# Battery-Voltage-Measure.net
KiCad netlist of a schematic drawn in EAGLE
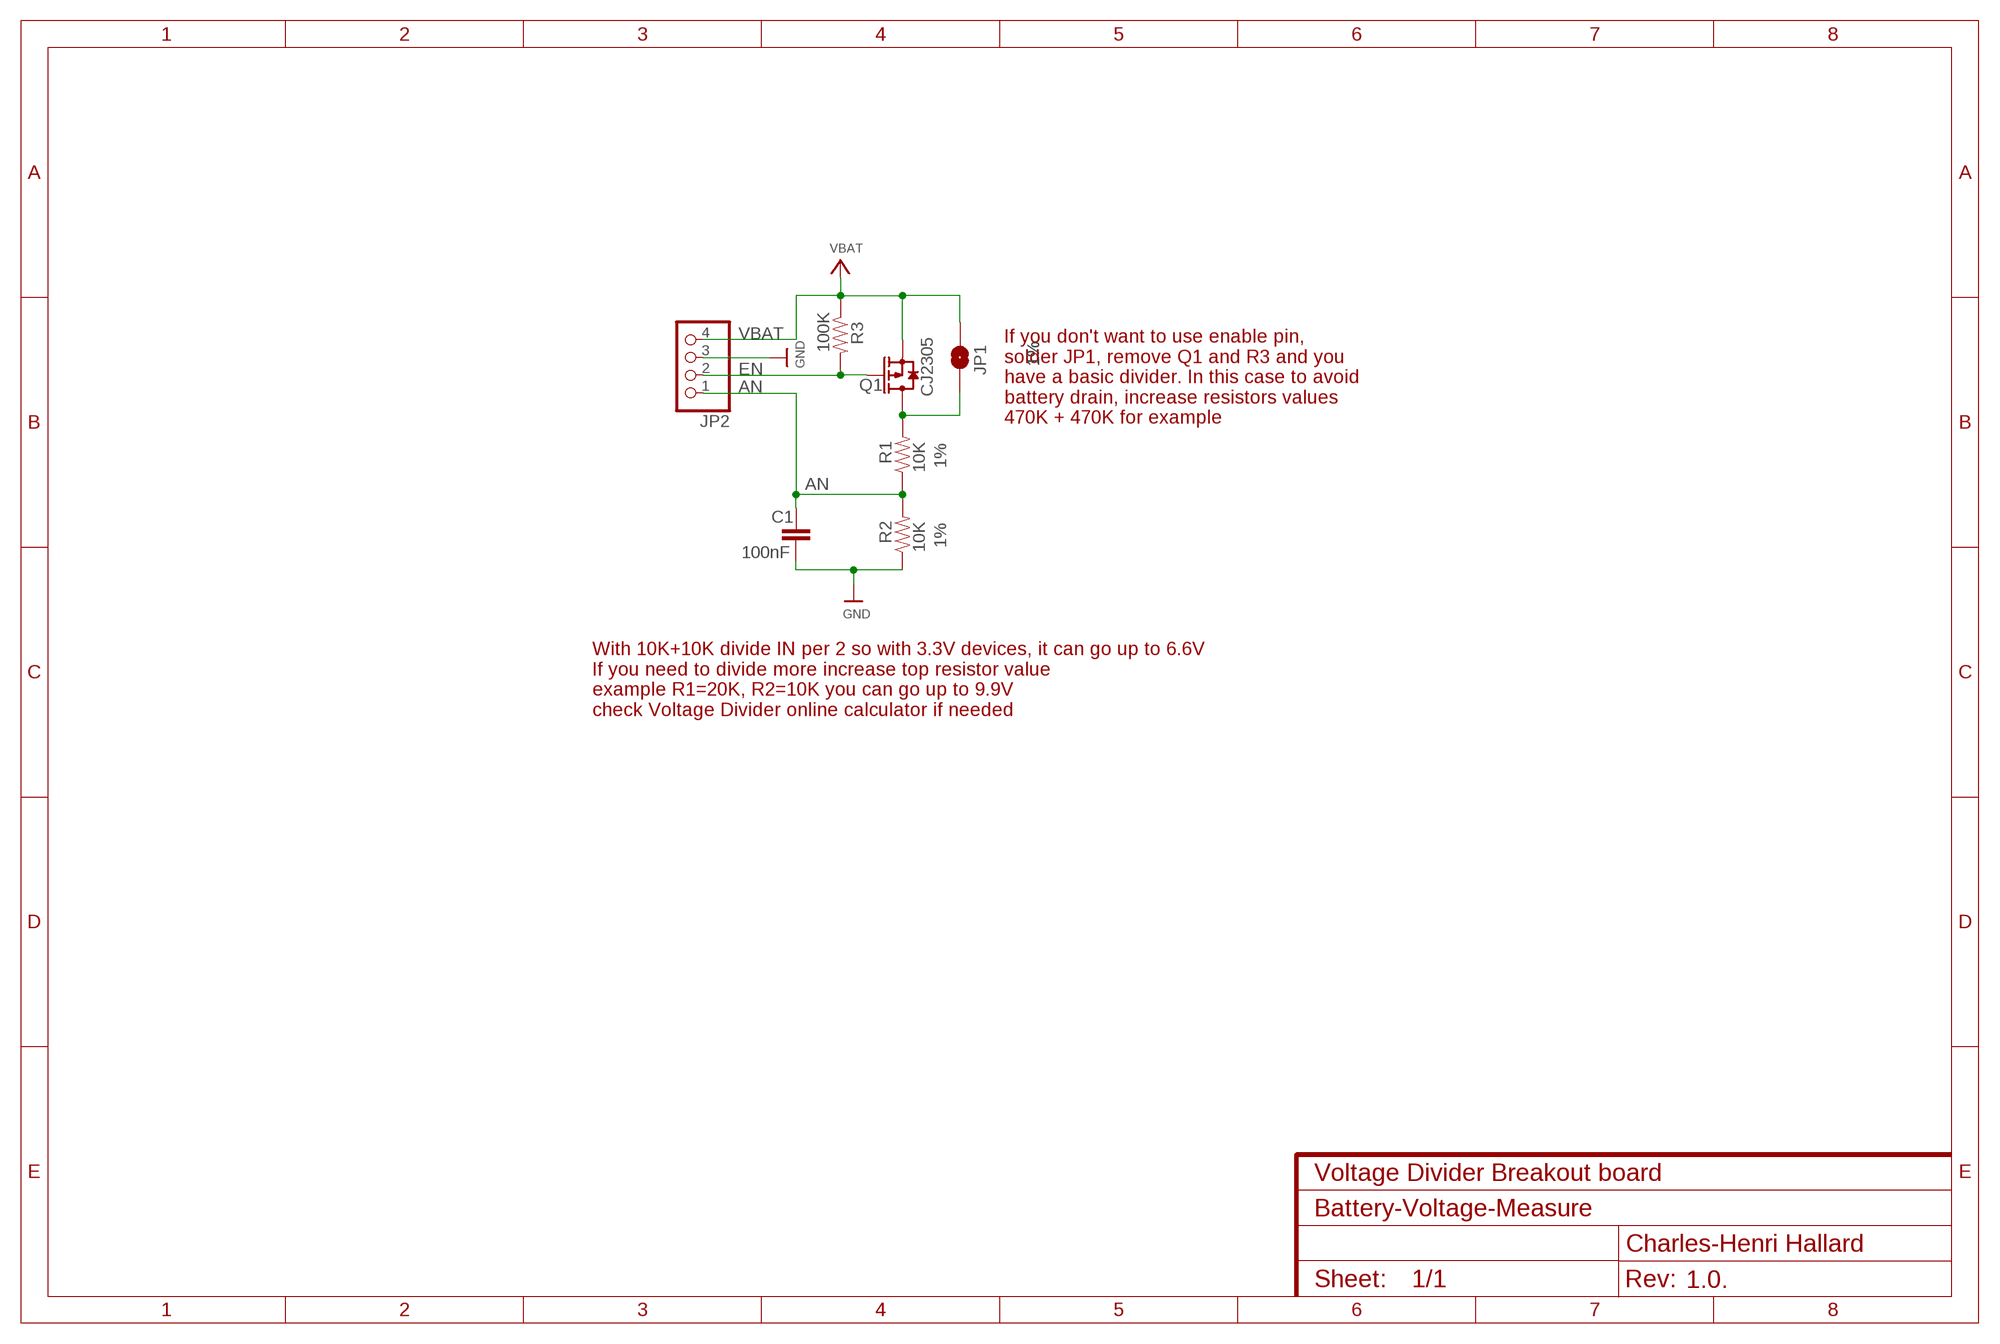
[diagram p0: schematic, sheet 1]

(export (version "E")
  (design (tool "Eeschema 10.0.6"))
  (components
    (comp (ref "C1")
      (value "100nF")
      (footprint "eagle-import:0805-CAP")
      (libsource (lib "eagle-import") (part "CAP0805-CAP"))
    )
    (comp (ref "JP1")
      (value "JUMPER-SMT_2_NO_SILK")
      (footprint "eagle-import:SMT-JUMPER_2_NO_SILK")
      (libsource (lib "eagle-import") (part "JUMPER-SMT_2_NO_SILK"))
    )
    (comp (ref "JP2")
      (value "HEADER-1X476MIL")
      (footprint "eagle-import:1X04_ROUND_76")
      (libsource (lib "eagle-import") (part "HEADER-1X476MIL"))
    )
    (comp (ref "Q1")
      (value "CJ2305")
      (footprint "eagle-import:SOT23")
      (libsource (lib "eagle-import") (part "MOSFET-P-044021001"))
    )
    (comp (ref "R1")
      (value "10K")
      (footprint "eagle-import:0805-RES")
      (libsource (lib "eagle-import") (part "_c2h_RESISTOR0805-RES"))
    )
    (comp (ref "R2")
      (value "10K")
      (footprint "eagle-import:0805-RES")
      (libsource (lib "eagle-import") (part "_c2h_RESISTOR0805-RES"))
    )
    (comp (ref "R3")
      (value "100K")
      (footprint "eagle-import:0805-RES")
      (libsource (lib "eagle-import") (part "RESISTOR0805-RES"))
    )
  )
  (nets
    (net (code "1") (name "/AN") (class "Default")
      (node (ref "C1") (pin "1") (pinfunction "1_1") (pintype "passive"))
      (node (ref "JP2") (pin "1") (pinfunction "1_1") (pintype "passive"))
      (node (ref "R1") (pin "1") (pinfunction "1_1") (pintype "passive"))
      (node (ref "R2") (pin "2") (pinfunction "2_2") (pintype "passive"))
    )
    (net (code "2") (name "/EN") (class "Default")
      (node (ref "JP2") (pin "2") (pinfunction "2_2") (pintype "passive"))
      (node (ref "Q1") (pin "1") (pinfunction "G_1") (pintype "passive"))
      (node (ref "R3") (pin "2") (pinfunction "2_2") (pintype "passive"))
    )
    (net (code "3") (name "GND") (class "Default")
      (node (ref "C1") (pin "2") (pinfunction "2_2") (pintype "passive"))
      (node (ref "JP2") (pin "3") (pinfunction "3_3") (pintype "passive"))
      (node (ref "R2") (pin "1") (pinfunction "1_1") (pintype "passive"))
    )
    (net (code "4") (name "Net-(Q1-D)") (class "Default")
      (node (ref "JP1") (pin "1") (pinfunction "1_1") (pintype "passive"))
      (node (ref "Q1") (pin "3") (pinfunction "D_3") (pintype "passive"))
      (node (ref "R1") (pin "2") (pinfunction "2_2") (pintype "passive"))
    )
    (net (code "5") (name "VBAT") (class "Default")
      (node (ref "JP1") (pin "2") (pinfunction "2_2") (pintype "passive"))
      (node (ref "JP2") (pin "4") (pinfunction "4_4") (pintype "passive"))
      (node (ref "Q1") (pin "2") (pinfunction "S_2") (pintype "passive"))
      (node (ref "R3") (pin "1") (pinfunction "1_1") (pintype "passive"))
    )
  )
)
